# pyIMU.net
KiCad netlist of a schematic drawn in EAGLE
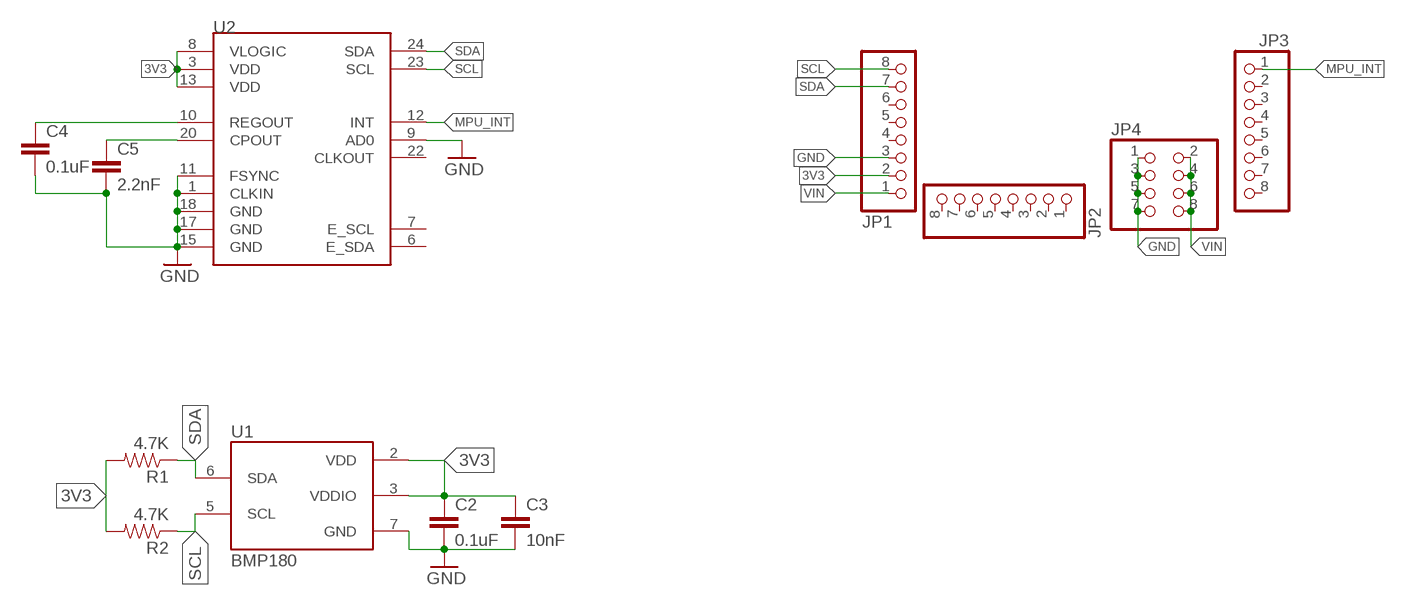
[diagram p0: schematic, sheet 1]

(export (version "E")
  (design (tool "Eeschema 10.0.6"))
  (components
    (comp (ref "C2")
      (value "0.1uF")
      (footprint "eagle-import:0603-CAP")
      (libsource (lib "eagle-import") (part "0.1UF-25V(+80/-20%)(0603)"))
    )
    (comp (ref "C3")
      (value "10nF")
      (footprint "eagle-import:0603-CAP")
      (libsource (lib "eagle-import") (part "10NF/10000PF-50V-10%(0603)"))
    )
    (comp (ref "C4")
      (value "0.1uF")
      (footprint "eagle-import:0603-CAP")
      (libsource (lib "eagle-import") (part "0.1UF-25V(+80/-20%)(0603)"))
    )
    (comp (ref "C5")
      (value "2.2nF")
      (footprint "eagle-import:0603-CAP")
      (libsource (lib "eagle-import") (part "2.2NF/2200PF-50V-10%(0603)"))
    )
    (comp (ref "JP1")
      (value "PINHD-1X8")
      (footprint "eagle-import:1X08")
      (libsource (lib "eagle-import") (part "PINHD-1X8"))
    )
    (comp (ref "JP2")
      (value "PINHD-1X8")
      (footprint "eagle-import:1X08")
      (libsource (lib "eagle-import") (part "PINHD-1X8"))
    )
    (comp (ref "JP3")
      (value "PINHD-1X8")
      (footprint "eagle-import:1X08")
      (libsource (lib "eagle-import") (part "PINHD-1X8"))
    )
    (comp (ref "JP4")
      (value "PINHD-2X4")
      (footprint "eagle-import:2X04")
      (libsource (lib "eagle-import") (part "PINHD-2X4"))
    )
    (comp (ref "R1")
      (value "4.7K")
      (footprint "eagle-import:0603-RES")
      (libsource (lib "eagle-import") (part "4.7KOHM1/10W1%(0603)"))
    )
    (comp (ref "R2")
      (value "4.7K")
      (footprint "eagle-import:0603-RES")
      (libsource (lib "eagle-import") (part "4.7KOHM1/10W1%(0603)"))
    )
    (comp (ref "U1")
      (value "BMP180")
      (footprint "eagle-import:BMP180")
      (libsource (lib "eagle-import") (part "BMP180"))
    )
    (comp (ref "U2")
      (value "MPU-9150QFN-24-NP")
      (footprint "eagle-import:QFN-24-NP")
      (libsource (lib "eagle-import") (part "MPU-9150QFN-24-NP"))
    )
  )
  (nets
    (net (code "1") (name "3V3") (class "Default")
      (node (ref "C2") (pin "1") (pinfunction "1_1") (pintype "passive"))
      (node (ref "C3") (pin "1") (pinfunction "1_1") (pintype "passive"))
      (node (ref "JP1") (pin "2") (pinfunction "2_2") (pintype "passive"))
      (node (ref "R1") (pin "2") (pinfunction "2_2") (pintype "passive"))
      (node (ref "R2") (pin "2") (pinfunction "2_2") (pintype "passive"))
      (node (ref "U1") (pin "2") (pinfunction "VDD_2") (pintype "power_in"))
      (node (ref "U1") (pin "3") (pinfunction "VDDIO_3") (pintype "power_in"))
      (node (ref "U2") (pin "13") (pinfunction "VDD_13") (pintype "bidirectional"))
      (node (ref "U2") (pin "3") (pinfunction "VDD_3") (pintype "bidirectional"))
      (node (ref "U2") (pin "8") (pinfunction "VLOGIC_8") (pintype "bidirectional"))
    )
    (net (code "2") (name "GND") (class "Default")
      (node (ref "C2") (pin "2") (pinfunction "2_2") (pintype "passive"))
      (node (ref "C3") (pin "2") (pinfunction "2_2") (pintype "passive"))
      (node (ref "C4") (pin "2") (pinfunction "2_2") (pintype "passive"))
      (node (ref "C5") (pin "2") (pinfunction "2_2") (pintype "passive"))
      (node (ref "JP1") (pin "3") (pinfunction "3_3") (pintype "passive"))
      (node (ref "JP4") (pin "1") (pinfunction "1_1") (pintype "passive"))
      (node (ref "JP4") (pin "3") (pinfunction "3_3") (pintype "passive"))
      (node (ref "JP4") (pin "5") (pinfunction "5_5") (pintype "passive"))
      (node (ref "JP4") (pin "7") (pinfunction "7_7") (pintype "passive"))
      (node (ref "U1") (pin "7") (pinfunction "GND_7") (pintype "power_in"))
      (node (ref "U2") (pin "1") (pinfunction "CLKIN_1") (pintype "bidirectional"))
      (node (ref "U2") (pin "11") (pinfunction "FSYNC_11") (pintype "bidirectional"))
      (node (ref "U2") (pin "15") (pinfunction "GND_15") (pintype "bidirectional"))
      (node (ref "U2") (pin "17") (pinfunction "GND_17") (pintype "bidirectional"))
      (node (ref "U2") (pin "18") (pinfunction "GND_18") (pintype "bidirectional"))
      (node (ref "U2") (pin "9") (pinfunction "AD0_9") (pintype "bidirectional"))
    )
    (net (code "3") (name "MPU_INT") (class "Default")
      (node (ref "JP3") (pin "1") (pinfunction "1_1") (pintype "passive"))
      (node (ref "U2") (pin "12") (pinfunction "INT_12") (pintype "bidirectional"))
    )
    (net (code "4") (name "Net-(U2-CPOUT)") (class "Default")
      (node (ref "C5") (pin "1") (pinfunction "1_1") (pintype "passive"))
      (node (ref "U2") (pin "20") (pinfunction "CPOUT_20") (pintype "bidirectional"))
    )
    (net (code "5") (name "Net-(U2-REGOUT)") (class "Default")
      (node (ref "C4") (pin "1") (pinfunction "1_1") (pintype "passive"))
      (node (ref "U2") (pin "10") (pinfunction "REGOUT_10") (pintype "bidirectional"))
    )
    (net (code "6") (name "SCL") (class "Default")
      (node (ref "JP1") (pin "8") (pinfunction "8_8") (pintype "passive"))
      (node (ref "R2") (pin "1") (pinfunction "1_1") (pintype "passive"))
      (node (ref "U1") (pin "5") (pinfunction "SCL_5") (pintype "input"))
      (node (ref "U2") (pin "23") (pinfunction "SCL_23") (pintype "bidirectional"))
    )
    (net (code "7") (name "SDA") (class "Default")
      (node (ref "JP1") (pin "7") (pinfunction "7_7") (pintype "passive"))
      (node (ref "R1") (pin "1") (pinfunction "1_1") (pintype "passive"))
      (node (ref "U1") (pin "6") (pinfunction "SDA_6") (pintype "bidirectional"))
      (node (ref "U2") (pin "24") (pinfunction "SDA_24") (pintype "bidirectional"))
    )
    (net (code "8") (name "VIN") (class "Default")
      (node (ref "JP1") (pin "1") (pinfunction "1_1") (pintype "passive"))
      (node (ref "JP4") (pin "2") (pinfunction "2_2") (pintype "passive"))
      (node (ref "JP4") (pin "4") (pinfunction "4_4") (pintype "passive"))
      (node (ref "JP4") (pin "6") (pinfunction "6_6") (pintype "passive"))
      (node (ref "JP4") (pin "8") (pinfunction "8_8") (pintype "passive"))
    )
    (net (code "9") (name "unconnected-(JP1-Pad4)") (class "Default")
      (node (ref "JP1") (pin "4") (pinfunction "4_4") (pintype "passive"))
    )
    (net (code "10") (name "unconnected-(JP1-Pad5)") (class "Default")
      (node (ref "JP1") (pin "5") (pinfunction "5_5") (pintype "passive"))
    )
    (net (code "11") (name "unconnected-(JP1-Pad6)") (class "Default")
      (node (ref "JP1") (pin "6") (pinfunction "6_6") (pintype "passive"))
    )
    (net (code "12") (name "unconnected-(JP2-Pad1)") (class "Default")
      (node (ref "JP2") (pin "1") (pinfunction "1_1") (pintype "passive"))
    )
    (net (code "13") (name "unconnected-(JP2-Pad2)") (class "Default")
      (node (ref "JP2") (pin "2") (pinfunction "2_2") (pintype "passive"))
    )
    (net (code "14") (name "unconnected-(JP2-Pad3)") (class "Default")
      (node (ref "JP2") (pin "3") (pinfunction "3_3") (pintype "passive"))
    )
    (net (code "15") (name "unconnected-(JP2-Pad4)") (class "Default")
      (node (ref "JP2") (pin "4") (pinfunction "4_4") (pintype "passive"))
    )
    (net (code "16") (name "unconnected-(JP2-Pad5)") (class "Default")
      (node (ref "JP2") (pin "5") (pinfunction "5_5") (pintype "passive"))
    )
    (net (code "17") (name "unconnected-(JP2-Pad6)") (class "Default")
      (node (ref "JP2") (pin "6") (pinfunction "6_6") (pintype "passive"))
    )
    (net (code "18") (name "unconnected-(JP2-Pad7)") (class "Default")
      (node (ref "JP2") (pin "7") (pinfunction "7_7") (pintype "passive"))
    )
    (net (code "19") (name "unconnected-(JP2-Pad8)") (class "Default")
      (node (ref "JP2") (pin "8") (pinfunction "8_8") (pintype "passive"))
    )
    (net (code "20") (name "unconnected-(JP3-Pad2)") (class "Default")
      (node (ref "JP3") (pin "2") (pinfunction "2_2") (pintype "passive"))
    )
    (net (code "21") (name "unconnected-(JP3-Pad3)") (class "Default")
      (node (ref "JP3") (pin "3") (pinfunction "3_3") (pintype "passive"))
    )
    (net (code "22") (name "unconnected-(JP3-Pad4)") (class "Default")
      (node (ref "JP3") (pin "4") (pinfunction "4_4") (pintype "passive"))
    )
    (net (code "23") (name "unconnected-(JP3-Pad5)") (class "Default")
      (node (ref "JP3") (pin "5") (pinfunction "5_5") (pintype "passive"))
    )
    (net (code "24") (name "unconnected-(JP3-Pad6)") (class "Default")
      (node (ref "JP3") (pin "6") (pinfunction "6_6") (pintype "passive"))
    )
    (net (code "25") (name "unconnected-(JP3-Pad7)") (class "Default")
      (node (ref "JP3") (pin "7") (pinfunction "7_7") (pintype "passive"))
    )
    (net (code "26") (name "unconnected-(JP3-Pad8)") (class "Default")
      (node (ref "JP3") (pin "8") (pinfunction "8_8") (pintype "passive"))
    )
    (net (code "27") (name "unconnected-(U2-CLKOUT-Pad22)") (class "Default")
      (node (ref "U2") (pin "22") (pinfunction "CLKOUT_22") (pintype "bidirectional"))
    )
    (net (code "28") (name "unconnected-(U2-E_SCL-Pad7)") (class "Default")
      (node (ref "U2") (pin "7") (pinfunction "E_SCL_7") (pintype "bidirectional"))
    )
    (net (code "29") (name "unconnected-(U2-E_SDA-Pad6)") (class "Default")
      (node (ref "U2") (pin "6") (pinfunction "E_SDA_6") (pintype "bidirectional"))
    )
  )
)
